# ZYNQ-PL.net
KiCad netlist of a schematic drawn in Altium Designer
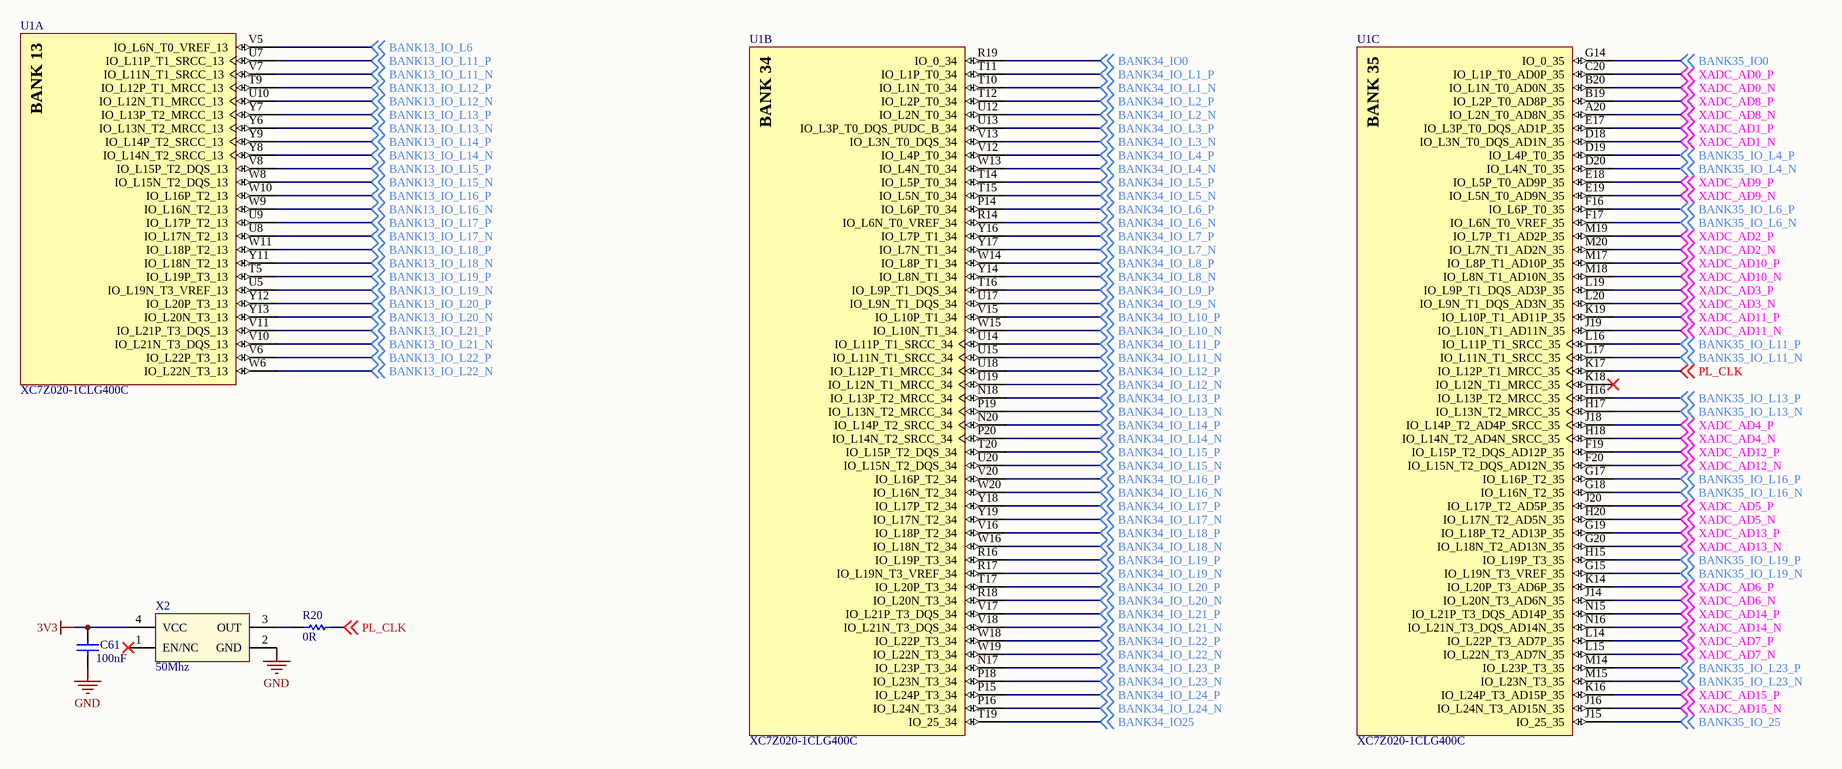
[diagram p0: ZYNQ-PL.SchDoc]

(export (version "E")
  (design (tool "Eeschema 10.0.6"))
  (components
    (comp (ref "C61")
      (value "100nF")
      (footprint "CAPC1005X55X25LL05T10")
      (fields (field (name "PART NUMBER") "GRM155R71H104KE14D") (field (name "MANUFACTURER") "Murata"))
      (libsource (lib "Altium Content Vault") (part "CAP"))
    )
    (comp (ref "R20")
      (value "0R")
      (footprint "RESC1005X40X25LL05T05")
      (fields (field (name "MANUFACTURER") "Panasonic") (field (name "PART NUMBER") "ERJ-2RKF40R2X"))
      (libsource (lib "Altium Content Vault") (part "RES"))
    )
    (comp (ref "U1")
      (value "XC7Z020-1CLG400C")
      (footprint "CLG400")
      (fields (field (name "GENERIC PART NUMBER") "XC7Z020"))
      (libsource (lib "Altium Content Vault") (part "XNLX-XC7Z020-CLG400"))
    )
    (comp (ref "X2")
      (value "50Mhz")
      (footprint "OSC-3225-4P")
      (description "4脚有源晶振(振荡器)")
      (libsource (lib "0.1 - 电阻-电容-电感-保险丝-晶振-晶体-磁珠-电位器-法拉电容-馈通电容") (part "XTAL-ACT-4P"))
    )
  )
  (nets
    (net (code "1") (name "3V3") (class "Default")
      (node (ref "C61") (pin "2") (pinfunction "2_2") (pintype "passive"))
      (node (ref "X2") (pin "4") (pinfunction "VCC_4") (pintype "passive"))
    )
    (net (code "2") (name "BANK13_IO_L6") (class "Default")
      (node (ref "U1") (pin "V5") (pinfunction "IO_L6N_T0_VREF_13_V5") (pintype "bidirectional"))
    )
    (net (code "3") (name "BANK13_IO_L11_N") (class "Default")
      (node (ref "U1") (pin "V7") (pinfunction "IO_L11N_T1_SRCC_13_V7") (pintype "bidirectional"))
    )
    (net (code "4") (name "BANK13_IO_L11_P") (class "Default")
      (node (ref "U1") (pin "U7") (pinfunction "IO_L11P_T1_SRCC_13_U7") (pintype "bidirectional"))
    )
    (net (code "5") (name "BANK13_IO_L12_N") (class "Default")
      (node (ref "U1") (pin "U10") (pinfunction "IO_L12N_T1_MRCC_13_U10") (pintype "bidirectional"))
    )
    (net (code "6") (name "BANK13_IO_L12_P") (class "Default")
      (node (ref "U1") (pin "T9") (pinfunction "IO_L12P_T1_MRCC_13_T9") (pintype "bidirectional"))
    )
    (net (code "7") (name "BANK13_IO_L13_N") (class "Default")
      (node (ref "U1") (pin "Y6") (pinfunction "IO_L13N_T2_MRCC_13_Y6") (pintype "bidirectional"))
    )
    (net (code "8") (name "BANK13_IO_L13_P") (class "Default")
      (node (ref "U1") (pin "Y7") (pinfunction "IO_L13P_T2_MRCC_13_Y7") (pintype "bidirectional"))
    )
    (net (code "9") (name "BANK13_IO_L14_N") (class "Default")
      (node (ref "U1") (pin "Y8") (pinfunction "IO_L14N_T2_SRCC_13_Y8") (pintype "bidirectional"))
    )
    (net (code "10") (name "BANK13_IO_L14_P") (class "Default")
      (node (ref "U1") (pin "Y9") (pinfunction "IO_L14P_T2_SRCC_13_Y9") (pintype "bidirectional"))
    )
    (net (code "11") (name "BANK13_IO_L15_N") (class "Default")
      (node (ref "U1") (pin "W8") (pinfunction "IO_L15N_T2_DQS_13_W8") (pintype "bidirectional"))
    )
    (net (code "12") (name "BANK13_IO_L15_P") (class "Default")
      (node (ref "U1") (pin "V8") (pinfunction "IO_L15P_T2_DQS_13_V8") (pintype "bidirectional"))
    )
    (net (code "13") (name "BANK13_IO_L16_N") (class "Default")
      (node (ref "U1") (pin "W9") (pinfunction "IO_L16N_T2_13_W9") (pintype "bidirectional"))
    )
    (net (code "14") (name "BANK13_IO_L16_P") (class "Default")
      (node (ref "U1") (pin "W10") (pinfunction "IO_L16P_T2_13_W10") (pintype "bidirectional"))
    )
    (net (code "15") (name "BANK13_IO_L17_N") (class "Default")
      (node (ref "U1") (pin "U8") (pinfunction "IO_L17N_T2_13_U8") (pintype "bidirectional"))
    )
    (net (code "16") (name "BANK13_IO_L17_P") (class "Default")
      (node (ref "U1") (pin "U9") (pinfunction "IO_L17P_T2_13_U9") (pintype "bidirectional"))
    )
    (net (code "17") (name "BANK13_IO_L18_N") (class "Default")
      (node (ref "U1") (pin "Y11") (pinfunction "IO_L18N_T2_13_Y11") (pintype "bidirectional"))
    )
    (net (code "18") (name "BANK13_IO_L18_P") (class "Default")
      (node (ref "U1") (pin "W11") (pinfunction "IO_L18P_T2_13_W11") (pintype "bidirectional"))
    )
    (net (code "19") (name "BANK13_IO_L19_N") (class "Default")
      (node (ref "U1") (pin "U5") (pinfunction "IO_L19N_T3_VREF_13_U5") (pintype "bidirectional"))
    )
    (net (code "20") (name "BANK13_IO_L19_P") (class "Default")
      (node (ref "U1") (pin "T5") (pinfunction "IO_L19P_T3_13_T5") (pintype "bidirectional"))
    )
    (net (code "21") (name "BANK13_IO_L20_N") (class "Default")
      (node (ref "U1") (pin "Y13") (pinfunction "IO_L20N_T3_13_Y13") (pintype "bidirectional"))
    )
    (net (code "22") (name "BANK13_IO_L20_P") (class "Default")
      (node (ref "U1") (pin "Y12") (pinfunction "IO_L20P_T3_13_Y12") (pintype "bidirectional"))
    )
    (net (code "23") (name "BANK13_IO_L21_N") (class "Default")
      (node (ref "U1") (pin "V10") (pinfunction "IO_L21N_T3_DQS_13_V10") (pintype "bidirectional"))
    )
    (net (code "24") (name "BANK13_IO_L21_P") (class "Default")
      (node (ref "U1") (pin "V11") (pinfunction "IO_L21P_T3_DQS_13_V11") (pintype "bidirectional"))
    )
    (net (code "25") (name "BANK13_IO_L22_N") (class "Default")
      (node (ref "U1") (pin "W6") (pinfunction "IO_L22N_T3_13_W6") (pintype "bidirectional"))
    )
    (net (code "26") (name "BANK13_IO_L22_P") (class "Default")
      (node (ref "U1") (pin "V6") (pinfunction "IO_L22P_T3_13_V6") (pintype "bidirectional"))
    )
    (net (code "27") (name "BANK34_IO0") (class "Default")
      (node (ref "U1") (pin "R19") (pinfunction "IO_0_34_R19") (pintype "bidirectional"))
    )
    (net (code "28") (name "BANK34_IO25") (class "Default")
      (node (ref "U1") (pin "T19") (pinfunction "IO_25_34_T19") (pintype "bidirectional"))
    )
    (net (code "29") (name "BANK34_IO_L1_N") (class "Default")
      (node (ref "U1") (pin "T10") (pinfunction "IO_L1N_T0_34_T10") (pintype "bidirectional"))
    )
    (net (code "30") (name "BANK34_IO_L1_P") (class "Default")
      (node (ref "U1") (pin "T11") (pinfunction "IO_L1P_T0_34_T11") (pintype "bidirectional"))
    )
    (net (code "31") (name "BANK34_IO_L2_N") (class "Default")
      (node (ref "U1") (pin "U12") (pinfunction "IO_L2N_T0_34_U12") (pintype "bidirectional"))
    )
    (net (code "32") (name "BANK34_IO_L2_P") (class "Default")
      (node (ref "U1") (pin "T12") (pinfunction "IO_L2P_T0_34_T12") (pintype "bidirectional"))
    )
    (net (code "33") (name "BANK34_IO_L3_N") (class "Default")
      (node (ref "U1") (pin "V13") (pinfunction "IO_L3N_T0_DQS_34_V13") (pintype "bidirectional"))
    )
    (net (code "34") (name "BANK34_IO_L3_P") (class "Default")
      (node (ref "U1") (pin "U13") (pinfunction "IO_L3P_T0_DQS_PUDC_B_34_U13") (pintype "bidirectional"))
    )
    (net (code "35") (name "BANK34_IO_L4_N") (class "Default")
      (node (ref "U1") (pin "W13") (pinfunction "IO_L4N_T0_34_W13") (pintype "bidirectional"))
    )
    (net (code "36") (name "BANK34_IO_L4_P") (class "Default")
      (node (ref "U1") (pin "V12") (pinfunction "IO_L4P_T0_34_V12") (pintype "bidirectional"))
    )
    (net (code "37") (name "BANK34_IO_L5_N") (class "Default")
      (node (ref "U1") (pin "T15") (pinfunction "IO_L5N_T0_34_T15") (pintype "bidirectional"))
    )
    (net (code "38") (name "BANK34_IO_L5_P") (class "Default")
      (node (ref "U1") (pin "T14") (pinfunction "IO_L5P_T0_34_T14") (pintype "bidirectional"))
    )
    (net (code "39") (name "BANK34_IO_L6_N") (class "Default")
      (node (ref "U1") (pin "R14") (pinfunction "IO_L6N_T0_VREF_34_R14") (pintype "bidirectional"))
    )
    (net (code "40") (name "BANK34_IO_L6_P") (class "Default")
      (node (ref "U1") (pin "P14") (pinfunction "IO_L6P_T0_34_P14") (pintype "bidirectional"))
    )
    (net (code "41") (name "BANK34_IO_L7_N") (class "Default")
      (node (ref "U1") (pin "Y17") (pinfunction "IO_L7N_T1_34_Y17") (pintype "bidirectional"))
    )
    (net (code "42") (name "BANK34_IO_L7_P") (class "Default")
      (node (ref "U1") (pin "Y16") (pinfunction "IO_L7P_T1_34_Y16") (pintype "bidirectional"))
    )
    (net (code "43") (name "BANK34_IO_L8_N") (class "Default")
      (node (ref "U1") (pin "Y14") (pinfunction "IO_L8N_T1_34_Y14") (pintype "bidirectional"))
    )
    (net (code "44") (name "BANK34_IO_L8_P") (class "Default")
      (node (ref "U1") (pin "W14") (pinfunction "IO_L8P_T1_34_W14") (pintype "bidirectional"))
    )
    (net (code "45") (name "BANK34_IO_L9_N") (class "Default")
      (node (ref "U1") (pin "U17") (pinfunction "IO_L9N_T1_DQS_34_U17") (pintype "bidirectional"))
    )
    (net (code "46") (name "BANK34_IO_L9_P") (class "Default")
      (node (ref "U1") (pin "T16") (pinfunction "IO_L9P_T1_DQS_34_T16") (pintype "bidirectional"))
    )
    (net (code "47") (name "BANK34_IO_L10_N") (class "Default")
      (node (ref "U1") (pin "W15") (pinfunction "IO_L10N_T1_34_W15") (pintype "bidirectional"))
    )
    (net (code "48") (name "BANK34_IO_L10_P") (class "Default")
      (node (ref "U1") (pin "V15") (pinfunction "IO_L10P_T1_34_V15") (pintype "bidirectional"))
    )
    (net (code "49") (name "BANK34_IO_L11_N") (class "Default")
      (node (ref "U1") (pin "U15") (pinfunction "IO_L11N_T1_SRCC_34_U15") (pintype "bidirectional"))
    )
    (net (code "50") (name "BANK34_IO_L11_P") (class "Default")
      (node (ref "U1") (pin "U14") (pinfunction "IO_L11P_T1_SRCC_34_U14") (pintype "bidirectional"))
    )
    (net (code "51") (name "BANK34_IO_L12_N") (class "Default")
      (node (ref "U1") (pin "U19") (pinfunction "IO_L12N_T1_MRCC_34_U19") (pintype "bidirectional"))
    )
    (net (code "52") (name "BANK34_IO_L12_P") (class "Default")
      (node (ref "U1") (pin "U18") (pinfunction "IO_L12P_T1_MRCC_34_U18") (pintype "bidirectional"))
    )
    (net (code "53") (name "BANK34_IO_L13_N") (class "Default")
      (node (ref "U1") (pin "P19") (pinfunction "IO_L13N_T2_MRCC_34_P19") (pintype "bidirectional"))
    )
    (net (code "54") (name "BANK34_IO_L13_P") (class "Default")
      (node (ref "U1") (pin "N18") (pinfunction "IO_L13P_T2_MRCC_34_N18") (pintype "bidirectional"))
    )
    (net (code "55") (name "BANK34_IO_L14_N") (class "Default")
      (node (ref "U1") (pin "P20") (pinfunction "IO_L14N_T2_SRCC_34_P20") (pintype "bidirectional"))
    )
    (net (code "56") (name "BANK34_IO_L14_P") (class "Default")
      (node (ref "U1") (pin "N20") (pinfunction "IO_L14P_T2_SRCC_34_N20") (pintype "bidirectional"))
    )
    (net (code "57") (name "BANK34_IO_L15_N") (class "Default")
      (node (ref "U1") (pin "U20") (pinfunction "IO_L15N_T2_DQS_34_U20") (pintype "bidirectional"))
    )
    (net (code "58") (name "BANK34_IO_L15_P") (class "Default")
      (node (ref "U1") (pin "T20") (pinfunction "IO_L15P_T2_DQS_34_T20") (pintype "bidirectional"))
    )
    (net (code "59") (name "BANK34_IO_L16_N") (class "Default")
      (node (ref "U1") (pin "W20") (pinfunction "IO_L16N_T2_34_W20") (pintype "bidirectional"))
    )
    (net (code "60") (name "BANK34_IO_L16_P") (class "Default")
      (node (ref "U1") (pin "V20") (pinfunction "IO_L16P_T2_34_V20") (pintype "bidirectional"))
    )
    (net (code "61") (name "BANK34_IO_L17_N") (class "Default")
      (node (ref "U1") (pin "Y19") (pinfunction "IO_L17N_T2_34_Y19") (pintype "bidirectional"))
    )
    (net (code "62") (name "BANK34_IO_L17_P") (class "Default")
      (node (ref "U1") (pin "Y18") (pinfunction "IO_L17P_T2_34_Y18") (pintype "bidirectional"))
    )
    (net (code "63") (name "BANK34_IO_L18_N") (class "Default")
      (node (ref "U1") (pin "W16") (pinfunction "IO_L18N_T2_34_W16") (pintype "bidirectional"))
    )
    (net (code "64") (name "BANK34_IO_L18_P") (class "Default")
      (node (ref "U1") (pin "V16") (pinfunction "IO_L18P_T2_34_V16") (pintype "bidirectional"))
    )
    (net (code "65") (name "BANK34_IO_L19_N") (class "Default")
      (node (ref "U1") (pin "R17") (pinfunction "IO_L19N_T3_VREF_34_R17") (pintype "bidirectional"))
    )
    (net (code "66") (name "BANK34_IO_L19_P") (class "Default")
      (node (ref "U1") (pin "R16") (pinfunction "IO_L19P_T3_34_R16") (pintype "bidirectional"))
    )
    (net (code "67") (name "BANK34_IO_L20_N") (class "Default")
      (node (ref "U1") (pin "R18") (pinfunction "IO_L20N_T3_34_R18") (pintype "bidirectional"))
    )
    (net (code "68") (name "BANK34_IO_L20_P") (class "Default")
      (node (ref "U1") (pin "T17") (pinfunction "IO_L20P_T3_34_T17") (pintype "bidirectional"))
    )
    (net (code "69") (name "BANK34_IO_L21_N") (class "Default")
      (node (ref "U1") (pin "V18") (pinfunction "IO_L21N_T3_DQS_34_V18") (pintype "bidirectional"))
    )
    (net (code "70") (name "BANK34_IO_L21_P") (class "Default")
      (node (ref "U1") (pin "V17") (pinfunction "IO_L21P_T3_DQS_34_V17") (pintype "bidirectional"))
    )
    (net (code "71") (name "BANK34_IO_L22_N") (class "Default")
      (node (ref "U1") (pin "W19") (pinfunction "IO_L22N_T3_34_W19") (pintype "bidirectional"))
    )
    (net (code "72") (name "BANK34_IO_L22_P") (class "Default")
      (node (ref "U1") (pin "W18") (pinfunction "IO_L22P_T3_34_W18") (pintype "bidirectional"))
    )
    (net (code "73") (name "BANK34_IO_L23_N") (class "Default")
      (node (ref "U1") (pin "P18") (pinfunction "IO_L23N_T3_34_P18") (pintype "bidirectional"))
    )
    (net (code "74") (name "BANK34_IO_L23_P") (class "Default")
      (node (ref "U1") (pin "N17") (pinfunction "IO_L23P_T3_34_N17") (pintype "bidirectional"))
    )
    (net (code "75") (name "BANK34_IO_L24_N") (class "Default")
      (node (ref "U1") (pin "P16") (pinfunction "IO_L24N_T3_34_P16") (pintype "bidirectional"))
    )
    (net (code "76") (name "BANK34_IO_L24_P") (class "Default")
      (node (ref "U1") (pin "P15") (pinfunction "IO_L24P_T3_34_P15") (pintype "bidirectional"))
    )
    (net (code "77") (name "BANK35_IO0") (class "Default")
      (node (ref "U1") (pin "G14") (pinfunction "IO_0_35_G14") (pintype "bidirectional"))
    )
    (net (code "78") (name "BANK35_IO_25") (class "Default")
      (node (ref "U1") (pin "J15") (pinfunction "IO_25_35_J15") (pintype "bidirectional"))
    )
    (net (code "79") (name "BANK35_IO_L4_N") (class "Default")
      (node (ref "U1") (pin "D20") (pinfunction "IO_L4N_T0_35_D20") (pintype "bidirectional"))
    )
    (net (code "80") (name "BANK35_IO_L4_P") (class "Default")
      (node (ref "U1") (pin "D19") (pinfunction "IO_L4P_T0_35_D19") (pintype "bidirectional"))
    )
    (net (code "81") (name "BANK35_IO_L6_N") (class "Default")
      (node (ref "U1") (pin "F17") (pinfunction "IO_L6N_T0_VREF_35_F17") (pintype "bidirectional"))
    )
    (net (code "82") (name "BANK35_IO_L6_P") (class "Default")
      (node (ref "U1") (pin "F16") (pinfunction "IO_L6P_T0_35_F16") (pintype "bidirectional"))
    )
    (net (code "83") (name "BANK35_IO_L11_N") (class "Default")
      (node (ref "U1") (pin "L17") (pinfunction "IO_L11N_T1_SRCC_35_L17") (pintype "bidirectional"))
    )
    (net (code "84") (name "BANK35_IO_L11_P") (class "Default")
      (node (ref "U1") (pin "L16") (pinfunction "IO_L11P_T1_SRCC_35_L16") (pintype "bidirectional"))
    )
    (net (code "85") (name "BANK35_IO_L13_N") (class "Default")
      (node (ref "U1") (pin "H17") (pinfunction "IO_L13N_T2_MRCC_35_H17") (pintype "bidirectional"))
    )
    (net (code "86") (name "BANK35_IO_L13_P") (class "Default")
      (node (ref "U1") (pin "H16") (pinfunction "IO_L13P_T2_MRCC_35_H16") (pintype "bidirectional"))
    )
    (net (code "87") (name "BANK35_IO_L16_N") (class "Default")
      (node (ref "U1") (pin "G18") (pinfunction "IO_L16N_T2_35_G18") (pintype "bidirectional"))
    )
    (net (code "88") (name "BANK35_IO_L16_P") (class "Default")
      (node (ref "U1") (pin "G17") (pinfunction "IO_L16P_T2_35_G17") (pintype "bidirectional"))
    )
    (net (code "89") (name "BANK35_IO_L19_N") (class "Default")
      (node (ref "U1") (pin "G15") (pinfunction "IO_L19N_T3_VREF_35_G15") (pintype "bidirectional"))
    )
    (net (code "90") (name "BANK35_IO_L19_P") (class "Default")
      (node (ref "U1") (pin "H15") (pinfunction "IO_L19P_T3_35_H15") (pintype "bidirectional"))
    )
    (net (code "91") (name "BANK35_IO_L23_N") (class "Default")
      (node (ref "U1") (pin "M15") (pinfunction "IO_L23N_T3_35_M15") (pintype "bidirectional"))
    )
    (net (code "92") (name "BANK35_IO_L23_P") (class "Default")
      (node (ref "U1") (pin "M14") (pinfunction "IO_L23P_T3_35_M14") (pintype "bidirectional"))
    )
    (net (code "93") (name "GND") (class "Default")
      (node (ref "C61") (pin "1") (pinfunction "1_1") (pintype "passive"))
      (node (ref "X2") (pin "2") (pinfunction "GND_2") (pintype "passive"))
    )
    (net (code "94") (name "Net-(X2-OUT)") (class "Default")
      (node (ref "R20") (pin "1") (pinfunction "1_1") (pintype "passive"))
      (node (ref "X2") (pin "3") (pinfunction "OUT_3") (pintype "passive"))
    )
    (net (code "95") (name "PL_CLK") (class "Default")
      (node (ref "R20") (pin "2") (pinfunction "2_2") (pintype "passive"))
      (node (ref "U1") (pin "K17") (pinfunction "IO_L12P_T1_MRCC_35_K17") (pintype "bidirectional"))
    )
    (net (code "96") (name "XADC_AD0_N") (class "Default")
      (node (ref "U1") (pin "B20") (pinfunction "IO_L1N_T0_AD0N_35_B20") (pintype "bidirectional"))
    )
    (net (code "97") (name "XADC_AD0_P") (class "Default")
      (node (ref "U1") (pin "C20") (pinfunction "IO_L1P_T0_AD0P_35_C20") (pintype "bidirectional"))
    )
    (net (code "98") (name "XADC_AD1_N") (class "Default")
      (node (ref "U1") (pin "D18") (pinfunction "IO_L3N_T0_DQS_AD1N_35_D18") (pintype "bidirectional"))
    )
    (net (code "99") (name "XADC_AD1_P") (class "Default")
      (node (ref "U1") (pin "E17") (pinfunction "IO_L3P_T0_DQS_AD1P_35_E17") (pintype "bidirectional"))
    )
    (net (code "100") (name "XADC_AD2_N") (class "Default")
      (node (ref "U1") (pin "M20") (pinfunction "IO_L7N_T1_AD2N_35_M20") (pintype "bidirectional"))
    )
    (net (code "101") (name "XADC_AD2_P") (class "Default")
      (node (ref "U1") (pin "M19") (pinfunction "IO_L7P_T1_AD2P_35_M19") (pintype "bidirectional"))
    )
    (net (code "102") (name "XADC_AD3_N") (class "Default")
      (node (ref "U1") (pin "L20") (pinfunction "IO_L9N_T1_DQS_AD3N_35_L20") (pintype "bidirectional"))
    )
    (net (code "103") (name "XADC_AD3_P") (class "Default")
      (node (ref "U1") (pin "L19") (pinfunction "IO_L9P_T1_DQS_AD3P_35_L19") (pintype "bidirectional"))
    )
    (net (code "104") (name "XADC_AD4_N") (class "Default")
      (node (ref "U1") (pin "H18") (pinfunction "IO_L14N_T2_AD4N_SRCC_35_H18") (pintype "bidirectional"))
    )
    (net (code "105") (name "XADC_AD4_P") (class "Default")
      (node (ref "U1") (pin "J18") (pinfunction "IO_L14P_T2_AD4P_SRCC_35_J18") (pintype "bidirectional"))
    )
    (net (code "106") (name "XADC_AD5_N") (class "Default")
      (node (ref "U1") (pin "H20") (pinfunction "IO_L17N_T2_AD5N_35_H20") (pintype "bidirectional"))
    )
    (net (code "107") (name "XADC_AD5_P") (class "Default")
      (node (ref "U1") (pin "J20") (pinfunction "IO_L17P_T2_AD5P_35_J20") (pintype "bidirectional"))
    )
    (net (code "108") (name "XADC_AD6_N") (class "Default")
      (node (ref "U1") (pin "J14") (pinfunction "IO_L20N_T3_AD6N_35_J14") (pintype "bidirectional"))
    )
    (net (code "109") (name "XADC_AD6_P") (class "Default")
      (node (ref "U1") (pin "K14") (pinfunction "IO_L20P_T3_AD6P_35_K14") (pintype "bidirectional"))
    )
    (net (code "110") (name "XADC_AD7_N") (class "Default")
      (node (ref "U1") (pin "L15") (pinfunction "IO_L22N_T3_AD7N_35_L15") (pintype "bidirectional"))
    )
    (net (code "111") (name "XADC_AD7_P") (class "Default")
      (node (ref "U1") (pin "L14") (pinfunction "IO_L22P_T3_AD7P_35_L14") (pintype "bidirectional"))
    )
    (net (code "112") (name "XADC_AD8_N") (class "Default")
      (node (ref "U1") (pin "A20") (pinfunction "IO_L2N_T0_AD8N_35_A20") (pintype "bidirectional"))
    )
    (net (code "113") (name "XADC_AD8_P") (class "Default")
      (node (ref "U1") (pin "B19") (pinfunction "IO_L2P_T0_AD8P_35_B19") (pintype "bidirectional"))
    )
    (net (code "114") (name "XADC_AD9_N") (class "Default")
      (node (ref "U1") (pin "E19") (pinfunction "IO_L5N_T0_AD9N_35_E19") (pintype "bidirectional"))
    )
    (net (code "115") (name "XADC_AD9_P") (class "Default")
      (node (ref "U1") (pin "E18") (pinfunction "IO_L5P_T0_AD9P_35_E18") (pintype "bidirectional"))
    )
    (net (code "116") (name "XADC_AD10_N") (class "Default")
      (node (ref "U1") (pin "M18") (pinfunction "IO_L8N_T1_AD10N_35_M18") (pintype "bidirectional"))
    )
    (net (code "117") (name "XADC_AD10_P") (class "Default")
      (node (ref "U1") (pin "M17") (pinfunction "IO_L8P_T1_AD10P_35_M17") (pintype "bidirectional"))
    )
    (net (code "118") (name "XADC_AD11_N") (class "Default")
      (node (ref "U1") (pin "J19") (pinfunction "IO_L10N_T1_AD11N_35_J19") (pintype "bidirectional"))
    )
    (net (code "119") (name "XADC_AD11_P") (class "Default")
      (node (ref "U1") (pin "K19") (pinfunction "IO_L10P_T1_AD11P_35_K19") (pintype "bidirectional"))
    )
    (net (code "120") (name "XADC_AD12_N") (class "Default")
      (node (ref "U1") (pin "F20") (pinfunction "IO_L15N_T2_DQS_AD12N_35_F20") (pintype "bidirectional"))
    )
    (net (code "121") (name "XADC_AD12_P") (class "Default")
      (node (ref "U1") (pin "F19") (pinfunction "IO_L15P_T2_DQS_AD12P_35_F19") (pintype "bidirectional"))
    )
    (net (code "122") (name "XADC_AD13_N") (class "Default")
      (node (ref "U1") (pin "G20") (pinfunction "IO_L18N_T2_AD13N_35_G20") (pintype "bidirectional"))
    )
    (net (code "123") (name "XADC_AD13_P") (class "Default")
      (node (ref "U1") (pin "G19") (pinfunction "IO_L18P_T2_AD13P_35_G19") (pintype "bidirectional"))
    )
    (net (code "124") (name "XADC_AD14_N") (class "Default")
      (node (ref "U1") (pin "N16") (pinfunction "IO_L21N_T3_DQS_AD14N_35_N16") (pintype "bidirectional"))
    )
    (net (code "125") (name "XADC_AD14_P") (class "Default")
      (node (ref "U1") (pin "N15") (pinfunction "IO_L21P_T3_DQS_AD14P_35_N15") (pintype "bidirectional"))
    )
    (net (code "126") (name "XADC_AD15_N") (class "Default")
      (node (ref "U1") (pin "J16") (pinfunction "IO_L24N_T3_AD15N_35_J16") (pintype "bidirectional"))
    )
    (net (code "127") (name "XADC_AD15_P") (class "Default")
      (node (ref "U1") (pin "K16") (pinfunction "IO_L24P_T3_AD15P_35_K16") (pintype "bidirectional"))
    )
    (net (code "128") (name "unconnected-(U1C-IO_L12N_T1_MRCC_35-PadK18)") (class "Default")
      (node (ref "U1") (pin "K18") (pinfunction "IO_L12N_T1_MRCC_35_K18") (pintype "bidirectional+no_connect"))
    )
    (net (code "129") (name "unconnected-(X2-EN{slash}NC-Pad1)") (class "Default")
      (node (ref "X2") (pin "1") (pinfunction "EN/NC_1") (pintype "passive+no_connect"))
    )
  )
)
